# Sheet_1.net
KiCad netlist of a schematic drawn in Altium Designer
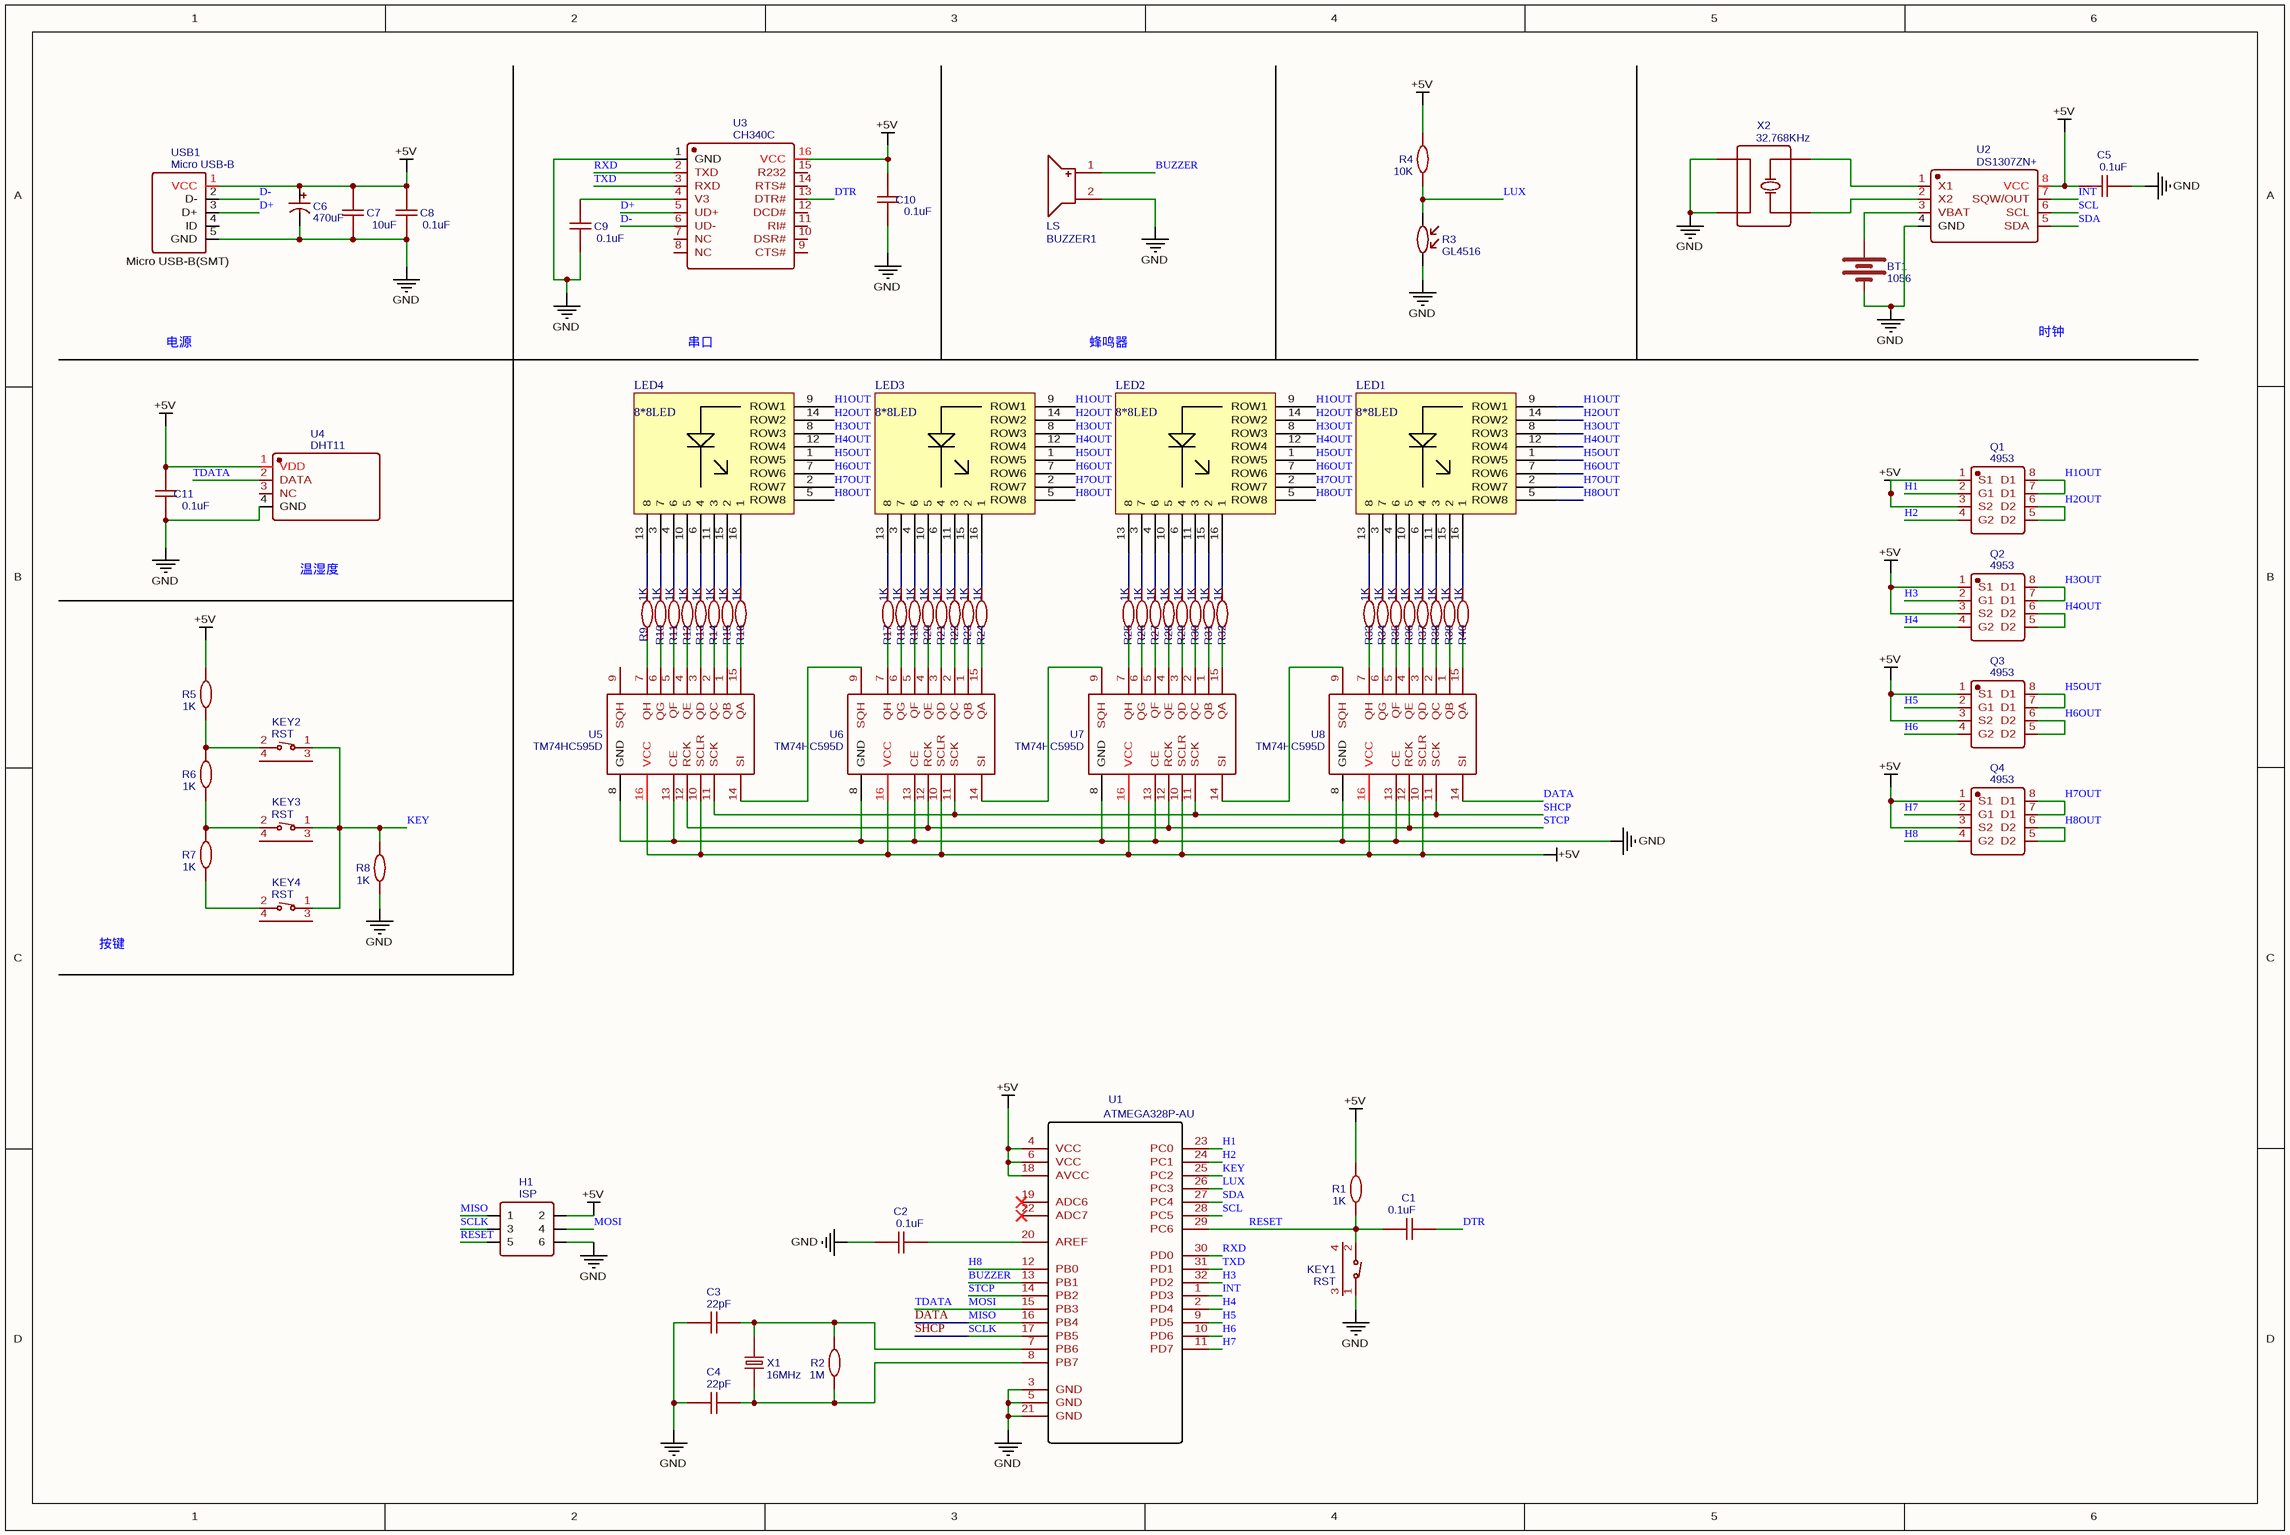
[diagram p0: Sheet_1.schdoc]

(export (version "E")
  (design (tool "Eeschema 10.0.6"))
  (components
    (comp (ref "BT1")
      (value "1056")
      (footprint "KEYSTONE_1056")
      (fields (field (name "BOM_SUPPLIER PART") "C238067"))
      (libsource (lib "altium-import") (part "root_3_1056_"))
    )
    (comp (ref "BUZZER1")
      (value "LS")
      (footprint "BUZZER-R6.0-2P-7.6MM")
      (fields
        (field (name "BOM_SUPPLIER PART") "C252943")
        (field (name "BOM_MANUFACTURER PART") "GMD12095YB-24V2400")
      )
      (libsource (lib "altium-import") (part "root_0_LS_"))
    )
    (comp (ref "C1")
      (value "0.1uF")
      (footprint "0603")
      (fields
        (field (name "BOM_SUPPLIER PART") "C138344")
        (field (name "BOM_MANUFACTURER PART") "CT41-0603-2F4-50V-0.1uF-M(N)")
      )
      (libsource (lib "altium-import") (part "root_1_0.1uF_"))
    )
    (comp (ref "C2")
      (value "0.1uF")
      (footprint "0603")
      (fields
        (field (name "BOM_SUPPLIER PART") "C138344")
        (field (name "BOM_MANUFACTURER PART") "CT41-0603-2F4-50V-0.1uF-M(N)")
      )
      (libsource (lib "altium-import") (part "root_1_0.1uF_"))
    )
    (comp (ref "C3")
      (value "22pF")
      (footprint "0603")
      (fields
        (field (name "BOM_MANUFACTURER PART") "0603CG220J500NT")
        (field (name "BOM_SUPPLIER PART") "C91701")
      )
      (libsource (lib "altium-import") (part "root_0_22pF_"))
    )
    (comp (ref "C4")
      (value "22pF")
      (footprint "0603")
      (fields
        (field (name "BOM_MANUFACTURER PART") "0603CG220J500NT")
        (field (name "BOM_SUPPLIER PART") "C91701")
      )
      (libsource (lib "altium-import") (part "root_0_22pF_"))
    )
    (comp (ref "C5")
      (value "0.1uF")
      (footprint "0603")
      (fields
        (field (name "BOM_SUPPLIER PART") "C138344")
        (field (name "BOM_MANUFACTURER PART") "CT41-0603-2F4-50V-0.1uF-M(N)")
      )
      (libsource (lib "altium-import") (part "root_3_0.1uF_"))
    )
    (comp (ref "C6")
      (value "470uF")
      (footprint "CASE-D_7343")
      (fields
        (field (name "BOM_MANUFACTURER PART") "T520D477M006ATE025")
        (field (name "BOM_SUPPLIER PART") "C156460")
      )
      (libsource (lib "altium-import") (part "root_3_470uF_"))
    )
    (comp (ref "C7")
      (value "10uF")
      (footprint "0603")
      (fields
        (field (name "BOM_SUPPLIER PART") "C138344")
        (field (name "BOM_MANUFACTURER PART") "CT41-0603-2F4-50V-0.1uF-M(N)")
      )
      (libsource (lib "altium-import") (part "root_2_10uF_"))
    )
    (comp (ref "C8")
      (value "0.1uF")
      (footprint "0603")
      (fields
        (field (name "BOM_SUPPLIER PART") "C138344")
        (field (name "BOM_MANUFACTURER PART") "CT41-0603-2F4-50V-0.1uF-M(N)")
      )
      (libsource (lib "altium-import") (part "root_2_0.1uF_"))
    )
    (comp (ref "C9")
      (value "0.1uF")
      (footprint "0603")
      (fields
        (field (name "BOM_SUPPLIER PART") "C138344")
        (field (name "BOM_MANUFACTURER PART") "CT41-0603-2F4-50V-0.1uF-M(N)")
      )
      (libsource (lib "altium-import") (part "root_2_0.1uF_"))
    )
    (comp (ref "C10")
      (value "0.1uF")
      (footprint "0603")
      (fields
        (field (name "BOM_SUPPLIER PART") "C138344")
        (field (name "BOM_MANUFACTURER PART") "CT41-0603-2F4-50V-0.1uF-M(N)")
      )
      (libsource (lib "altium-import") (part "root_2_0.1uF_"))
    )
    (comp (ref "C11")
      (value "0.1uF")
      (footprint "0603")
      (fields
        (field (name "BOM_SUPPLIER PART") "C138344")
        (field (name "BOM_MANUFACTURER PART") "CT41-0603-2F4-50V-0.1uF-M(N)")
      )
      (libsource (lib "altium-import") (part "root_2_0.1uF_"))
    )
    (comp (ref "H1")
      (value "ISP")
      (footprint "HDR-3X2/2.54")
      (fields
        (field (name "BOM_MANUFACTURER PART") "DS1023-2*3SF11")
        (field (name "BOM_SUPPLIER PART") "C92272")
      )
      (libsource (lib "altium-import") (part "root_0_ISP_"))
    )
    (comp (ref "KEY1")
      (value "RST")
      (footprint "SW-TH_BBJ6X6X5PH260G")
      (fields
        (field (name "BOM_SUPPLIER PART") "C71832")
        (field (name "BOM_MANUFACTURER PART") "Switch,6*6*5Plastic head,260G, 0.25mm,Side foot")
      )
      (libsource (lib "altium-import") (part "root_1_RST_"))
    )
    (comp (ref "KEY2")
      (value "RST")
      (footprint "SW-TH_BBJ6X6X5PH260G")
      (fields
        (field (name "BOM_SUPPLIER PART") "C71832")
        (field (name "BOM_MANUFACTURER PART") "Switch,6*6*5Plastic head,260G, 0.25mm,Side foot")
      )
      (libsource (lib "altium-import") (part "root_2_RST_"))
    )
    (comp (ref "KEY3")
      (value "RST")
      (footprint "SW-TH_BBJ6X6X5PH260G")
      (fields
        (field (name "BOM_SUPPLIER PART") "C71832")
        (field (name "BOM_MANUFACTURER PART") "Switch,6*6*5Plastic head,260G, 0.25mm,Side foot")
      )
      (libsource (lib "altium-import") (part "root_2_RST_"))
    )
    (comp (ref "KEY4")
      (value "RST")
      (footprint "SW-TH_BBJ6X6X5PH260G")
      (fields
        (field (name "BOM_SUPPLIER PART") "C71832")
        (field (name "BOM_MANUFACTURER PART") "Switch,6*6*5Plastic head,260G, 0.25mm,Side foot")
      )
      (libsource (lib "altium-import") (part "root_2_RST_"))
    )
    (comp (ref "LED1") (value "8*8LED") (footprint "8X8LED") (libsource (lib "Sheet_1") (part "8*8LED")))
    (comp (ref "LED2") (value "8*8LED") (footprint "8X8LED") (libsource (lib "Sheet_1") (part "8*8LED")))
    (comp (ref "LED3") (value "8*8LED") (footprint "8X8LED") (libsource (lib "Sheet_1") (part "8*8LED")))
    (comp (ref "LED4") (value "8*8LED") (footprint "8X8LED") (libsource (lib "Sheet_1") (part "8*8LED")))
    (comp (ref "Q1")
      (value "4953")
      (footprint "SOP-8")
      (fields (field (name "BOM_SUPPLIER PART") "C181099"))
      (libsource (lib "altium-import") (part "root_0_4953_"))
    )
    (comp (ref "Q2")
      (value "4953")
      (footprint "SOP-8")
      (fields (field (name "BOM_SUPPLIER PART") "C181099"))
      (libsource (lib "altium-import") (part "root_0_4953_"))
    )
    (comp (ref "Q3")
      (value "4953")
      (footprint "SOP-8")
      (fields (field (name "BOM_SUPPLIER PART") "C181099"))
      (libsource (lib "altium-import") (part "root_0_4953_"))
    )
    (comp (ref "Q4")
      (value "4953")
      (footprint "SOP-8")
      (fields (field (name "BOM_SUPPLIER PART") "C181099"))
      (libsource (lib "altium-import") (part "root_0_4953_"))
    )
    (comp (ref "R1")
      (value "1K")
      (footprint "0603")
      (fields
        (field (name "BOM_SUPPLIER PART") "C188364")
        (field (name "BOM_MANUFACTURER PART") "TR0603B1KP0525")
      )
      (libsource (lib "altium-import") (part "root_1_1K_"))
    )
    (comp (ref "R2")
      (value "1M")
      (footprint "0603")
      (fields
        (field (name "BOM_SUPPLIER PART") "C188364")
        (field (name "BOM_MANUFACTURER PART") "TR0603B1KP0525")
      )
      (libsource (lib "altium-import") (part "root_1_1M_"))
    )
    (comp (ref "R3")
      (value "GL4516")
      (footprint "RES-TH_L4.30-W3.60-L")
      (fields (field (name "BOM_SUPPLIER PART") "C125632"))
      (libsource (lib "altium-import") (part "root_3_GL4516_"))
    )
    (comp (ref "R4")
      (value "10K")
      (footprint "0603")
      (fields
        (field (name "BOM_SUPPLIER PART") "C188364")
        (field (name "BOM_MANUFACTURER PART") "TR0603B1KP0525")
      )
      (libsource (lib "altium-import") (part "root_1_10K_"))
    )
    (comp (ref "R5")
      (value "1K")
      (footprint "0603")
      (fields
        (field (name "BOM_SUPPLIER PART") "C188364")
        (field (name "BOM_MANUFACTURER PART") "TR0603B1KP0525")
      )
      (libsource (lib "altium-import") (part "root_1_1K_"))
    )
    (comp (ref "R6")
      (value "1K")
      (footprint "0603")
      (fields
        (field (name "BOM_SUPPLIER PART") "C188364")
        (field (name "BOM_MANUFACTURER PART") "TR0603B1KP0525")
      )
      (libsource (lib "altium-import") (part "root_1_1K_"))
    )
    (comp (ref "R7")
      (value "1K")
      (footprint "0603")
      (fields
        (field (name "BOM_SUPPLIER PART") "C188364")
        (field (name "BOM_MANUFACTURER PART") "TR0603B1KP0525")
      )
      (libsource (lib "altium-import") (part "root_1_1K_"))
    )
    (comp (ref "R8")
      (value "1K")
      (footprint "0603")
      (fields
        (field (name "BOM_SUPPLIER PART") "C188364")
        (field (name "BOM_MANUFACTURER PART") "TR0603B1KP0525")
      )
      (libsource (lib "altium-import") (part "root_1_1K_"))
    )
    (comp (ref "R9")
      (value "1K")
      (footprint "0603")
      (fields
        (field (name "BOM_SUPPLIER PART") "C188364")
        (field (name "BOM_MANUFACTURER PART") "TR0603B1KP0525")
      )
      (libsource (lib "altium-import") (part "root_1_1K_"))
    )
    (comp (ref "R10")
      (value "1K")
      (footprint "0603")
      (fields
        (field (name "BOM_SUPPLIER PART") "C188364")
        (field (name "BOM_MANUFACTURER PART") "TR0603B1KP0525")
      )
      (libsource (lib "altium-import") (part "root_1_1K_"))
    )
    (comp (ref "R11")
      (value "1K")
      (footprint "0603")
      (fields
        (field (name "BOM_SUPPLIER PART") "C188364")
        (field (name "BOM_MANUFACTURER PART") "TR0603B1KP0525")
      )
      (libsource (lib "altium-import") (part "root_1_1K_"))
    )
    (comp (ref "R12")
      (value "1K")
      (footprint "0603")
      (fields
        (field (name "BOM_SUPPLIER PART") "C188364")
        (field (name "BOM_MANUFACTURER PART") "TR0603B1KP0525")
      )
      (libsource (lib "altium-import") (part "root_1_1K_"))
    )
    (comp (ref "R13")
      (value "1K")
      (footprint "0603")
      (fields
        (field (name "BOM_SUPPLIER PART") "C188364")
        (field (name "BOM_MANUFACTURER PART") "TR0603B1KP0525")
      )
      (libsource (lib "altium-import") (part "root_1_1K_"))
    )
    (comp (ref "R14")
      (value "1K")
      (footprint "0603")
      (fields
        (field (name "BOM_SUPPLIER PART") "C188364")
        (field (name "BOM_MANUFACTURER PART") "TR0603B1KP0525")
      )
      (libsource (lib "altium-import") (part "root_1_1K_"))
    )
    (comp (ref "R15")
      (value "1K")
      (footprint "0603")
      (fields
        (field (name "BOM_SUPPLIER PART") "C188364")
        (field (name "BOM_MANUFACTURER PART") "TR0603B1KP0525")
      )
      (libsource (lib "altium-import") (part "root_1_1K_"))
    )
    (comp (ref "R16")
      (value "1K")
      (footprint "0603")
      (fields
        (field (name "BOM_SUPPLIER PART") "C188364")
        (field (name "BOM_MANUFACTURER PART") "TR0603B1KP0525")
      )
      (libsource (lib "altium-import") (part "root_1_1K_"))
    )
    (comp (ref "R17")
      (value "1K")
      (footprint "0603")
      (fields
        (field (name "BOM_SUPPLIER PART") "C188364")
        (field (name "BOM_MANUFACTURER PART") "TR0603B1KP0525")
      )
      (libsource (lib "altium-import") (part "root_1_1K_"))
    )
    (comp (ref "R18")
      (value "1K")
      (footprint "0603")
      (fields
        (field (name "BOM_SUPPLIER PART") "C188364")
        (field (name "BOM_MANUFACTURER PART") "TR0603B1KP0525")
      )
      (libsource (lib "altium-import") (part "root_1_1K_"))
    )
    (comp (ref "R19")
      (value "1K")
      (footprint "0603")
      (fields
        (field (name "BOM_SUPPLIER PART") "C188364")
        (field (name "BOM_MANUFACTURER PART") "TR0603B1KP0525")
      )
      (libsource (lib "altium-import") (part "root_1_1K_"))
    )
    (comp (ref "R20")
      (value "1K")
      (footprint "0603")
      (fields
        (field (name "BOM_SUPPLIER PART") "C188364")
        (field (name "BOM_MANUFACTURER PART") "TR0603B1KP0525")
      )
      (libsource (lib "altium-import") (part "root_1_1K_"))
    )
    (comp (ref "R21")
      (value "1K")
      (footprint "0603")
      (fields
        (field (name "BOM_SUPPLIER PART") "C188364")
        (field (name "BOM_MANUFACTURER PART") "TR0603B1KP0525")
      )
      (libsource (lib "altium-import") (part "root_1_1K_"))
    )
    (comp (ref "R22")
      (value "1K")
      (footprint "0603")
      (fields
        (field (name "BOM_SUPPLIER PART") "C188364")
        (field (name "BOM_MANUFACTURER PART") "TR0603B1KP0525")
      )
      (libsource (lib "altium-import") (part "root_1_1K_"))
    )
    (comp (ref "R23")
      (value "1K")
      (footprint "0603")
      (fields
        (field (name "BOM_SUPPLIER PART") "C188364")
        (field (name "BOM_MANUFACTURER PART") "TR0603B1KP0525")
      )
      (libsource (lib "altium-import") (part "root_1_1K_"))
    )
    (comp (ref "R24")
      (value "1K")
      (footprint "0603")
      (fields
        (field (name "BOM_SUPPLIER PART") "C188364")
        (field (name "BOM_MANUFACTURER PART") "TR0603B1KP0525")
      )
      (libsource (lib "altium-import") (part "root_1_1K_"))
    )
    (comp (ref "R25")
      (value "1K")
      (footprint "0603")
      (fields
        (field (name "BOM_SUPPLIER PART") "C188364")
        (field (name "BOM_MANUFACTURER PART") "TR0603B1KP0525")
      )
      (libsource (lib "altium-import") (part "root_1_1K_"))
    )
    (comp (ref "R26")
      (value "1K")
      (footprint "0603")
      (fields
        (field (name "BOM_SUPPLIER PART") "C188364")
        (field (name "BOM_MANUFACTURER PART") "TR0603B1KP0525")
      )
      (libsource (lib "altium-import") (part "root_1_1K_"))
    )
    (comp (ref "R27")
      (value "1K")
      (footprint "0603")
      (fields
        (field (name "BOM_SUPPLIER PART") "C188364")
        (field (name "BOM_MANUFACTURER PART") "TR0603B1KP0525")
      )
      (libsource (lib "altium-import") (part "root_1_1K_"))
    )
    (comp (ref "R28")
      (value "1K")
      (footprint "0603")
      (fields
        (field (name "BOM_SUPPLIER PART") "C188364")
        (field (name "BOM_MANUFACTURER PART") "TR0603B1KP0525")
      )
      (libsource (lib "altium-import") (part "root_1_1K_"))
    )
    (comp (ref "R29")
      (value "1K")
      (footprint "0603")
      (fields
        (field (name "BOM_SUPPLIER PART") "C188364")
        (field (name "BOM_MANUFACTURER PART") "TR0603B1KP0525")
      )
      (libsource (lib "altium-import") (part "root_1_1K_"))
    )
    (comp (ref "R30")
      (value "1K")
      (footprint "0603")
      (fields
        (field (name "BOM_SUPPLIER PART") "C188364")
        (field (name "BOM_MANUFACTURER PART") "TR0603B1KP0525")
      )
      (libsource (lib "altium-import") (part "root_1_1K_"))
    )
    (comp (ref "R31")
      (value "1K")
      (footprint "0603")
      (fields
        (field (name "BOM_SUPPLIER PART") "C188364")
        (field (name "BOM_MANUFACTURER PART") "TR0603B1KP0525")
      )
      (libsource (lib "altium-import") (part "root_1_1K_"))
    )
    (comp (ref "R32")
      (value "1K")
      (footprint "0603")
      (fields
        (field (name "BOM_SUPPLIER PART") "C188364")
        (field (name "BOM_MANUFACTURER PART") "TR0603B1KP0525")
      )
      (libsource (lib "altium-import") (part "root_1_1K_"))
    )
    (comp (ref "R33")
      (value "1K")
      (footprint "0603")
      (fields
        (field (name "BOM_SUPPLIER PART") "C188364")
        (field (name "BOM_MANUFACTURER PART") "TR0603B1KP0525")
      )
      (libsource (lib "altium-import") (part "root_1_1K_"))
    )
    (comp (ref "R34")
      (value "1K")
      (footprint "0603")
      (fields
        (field (name "BOM_SUPPLIER PART") "C188364")
        (field (name "BOM_MANUFACTURER PART") "TR0603B1KP0525")
      )
      (libsource (lib "altium-import") (part "root_1_1K_"))
    )
    (comp (ref "R35")
      (value "1K")
      (footprint "0603")
      (fields
        (field (name "BOM_SUPPLIER PART") "C188364")
        (field (name "BOM_MANUFACTURER PART") "TR0603B1KP0525")
      )
      (libsource (lib "altium-import") (part "root_1_1K_"))
    )
    (comp (ref "R36")
      (value "1K")
      (footprint "0603")
      (fields
        (field (name "BOM_SUPPLIER PART") "C188364")
        (field (name "BOM_MANUFACTURER PART") "TR0603B1KP0525")
      )
      (libsource (lib "altium-import") (part "root_1_1K_"))
    )
    (comp (ref "R37")
      (value "1K")
      (footprint "0603")
      (fields
        (field (name "BOM_SUPPLIER PART") "C188364")
        (field (name "BOM_MANUFACTURER PART") "TR0603B1KP0525")
      )
      (libsource (lib "altium-import") (part "root_1_1K_"))
    )
    (comp (ref "R38")
      (value "1K")
      (footprint "0603")
      (fields
        (field (name "BOM_SUPPLIER PART") "C188364")
        (field (name "BOM_MANUFACTURER PART") "TR0603B1KP0525")
      )
      (libsource (lib "altium-import") (part "root_1_1K_"))
    )
    (comp (ref "R39")
      (value "1K")
      (footprint "0603")
      (fields
        (field (name "BOM_SUPPLIER PART") "C188364")
        (field (name "BOM_MANUFACTURER PART") "TR0603B1KP0525")
      )
      (libsource (lib "altium-import") (part "root_1_1K_"))
    )
    (comp (ref "R40")
      (value "1K")
      (footprint "0603")
      (fields
        (field (name "BOM_SUPPLIER PART") "C188364")
        (field (name "BOM_MANUFACTURER PART") "TR0603B1KP0525")
      )
      (libsource (lib "altium-import") (part "root_1_1K_"))
    )
    (comp (ref "U1")
      (value "ATMEGA328P-AU")
      (footprint "TQFP-32_7X7X08P")
      (fields (field (name "BOM_SUPPLIER PART") "C14877"))
      (libsource (lib "altium-import") (part "root_0_ATMEGA328P-AU_"))
    )
    (comp (ref "U2")
      (value "DS1307ZN+")
      (footprint "SOP-8_150MIL")
      (fields (field (name "BOM_SUPPLIER PART") "C26858"))
      (libsource (lib "altium-import") (part "root_0_DS1307ZN+_"))
    )
    (comp (ref "U3")
      (value "CH340C")
      (footprint "SOP-16_150MIL")
      (fields (field (name "BOM_SUPPLIER PART") "C84681"))
      (libsource (lib "altium-import") (part "root_0_CH340C_"))
    )
    (comp (ref "U4")
      (value "DHT11")
      (footprint "DHT11")
      (fields (field (name "BOM_SUPPLIER PART") "C117051"))
      (libsource (lib "altium-import") (part "root_0_DHT11_"))
    )
    (comp (ref "U5")
      (value "TM74HC595D")
      (footprint "SOP-16_150MIL")
      (fields (field (name "BOM_SUPPLIER PART") "C79097"))
      (libsource (lib "altium-import") (part "root_1_TM74HC595D_"))
    )
    (comp (ref "U6")
      (value "TM74HC595D")
      (footprint "SOP-16_150MIL")
      (fields (field (name "BOM_SUPPLIER PART") "C79097"))
      (libsource (lib "altium-import") (part "root_1_TM74HC595D_"))
    )
    (comp (ref "U7")
      (value "TM74HC595D")
      (footprint "SOP-16_150MIL")
      (fields (field (name "BOM_SUPPLIER PART") "C79097"))
      (libsource (lib "altium-import") (part "root_1_TM74HC595D_"))
    )
    (comp (ref "U8")
      (value "TM74HC595D")
      (footprint "SOP-16_150MIL")
      (fields (field (name "BOM_SUPPLIER PART") "C79097"))
      (libsource (lib "altium-import") (part "root_1_TM74HC595D_"))
    )
    (comp (ref "USB1")
      (value "Micro USB-B")
      (footprint "MICRO-USB-12")
      (fields
        (field (name "BOM_MANUFACTURER PART") "Micro USB-B 5P_C40942")
        (field (name "BOM_SUPPLIER PART") "C40942")
      )
      (libsource (lib "altium-import") (part "root_0_Micro USB-B_"))
    )
    (comp (ref "X1")
      (value "16MHz")
      (footprint "49S-CRYSTAL")
      (fields
        (field (name "BOM_SUPPLIER PART") "C295075")
        (field (name "BOM_MANUFACTURER PART") "XIHCELNANF-16MHZ")
      )
      (libsource (lib "altium-import") (part "root_3_16MHz_"))
    )
    (comp (ref "X2")
      (value "32.768KHz")
      (footprint "MC-146")
      (fields
        (field (name "BOM_MANUFACTURER PART") "MC-14632.768kHz7.0pF20PPM")
        (field (name "BOM_SUPPLIER PART") "C94977")
      )
      (libsource (lib "altium-import") (part "root_2_32.768KHz_"))
    )
  )
  (nets
    (net (code "1") (name "+5V") (class "Default")
      (node (ref "C10") (pin "2") (pinfunction "2_2") (pintype "passive"))
      (node (ref "C11") (pin "2") (pinfunction "2_2") (pintype "passive"))
      (node (ref "C5") (pin "2") (pinfunction "2_2") (pintype "passive"))
      (node (ref "C6") (pin "1") (pinfunction "1_1") (pintype "passive"))
      (node (ref "C7") (pin "2") (pinfunction "2_2") (pintype "passive"))
      (node (ref "C8") (pin "2") (pinfunction "2_2") (pintype "passive"))
      (node (ref "H1") (pin "2") (pinfunction "2_2") (pintype "passive"))
      (node (ref "Q1") (pin "1") (pinfunction "S1_1") (pintype "passive"))
      (node (ref "Q1") (pin "3") (pinfunction "S2_3") (pintype "passive"))
      (node (ref "Q2") (pin "1") (pinfunction "S1_1") (pintype "passive"))
      (node (ref "Q2") (pin "3") (pinfunction "S2_3") (pintype "passive"))
      (node (ref "Q3") (pin "1") (pinfunction "S1_1") (pintype "passive"))
      (node (ref "Q3") (pin "3") (pinfunction "S2_3") (pintype "passive"))
      (node (ref "Q4") (pin "1") (pinfunction "S1_1") (pintype "passive"))
      (node (ref "Q4") (pin "3") (pinfunction "S2_3") (pintype "passive"))
      (node (ref "R1") (pin "2") (pinfunction "2_2") (pintype "passive"))
      (node (ref "R4") (pin "2") (pinfunction "2_2") (pintype "passive"))
      (node (ref "R5") (pin "2") (pinfunction "2_2") (pintype "passive"))
      (node (ref "U1") (pin "18") (pinfunction "AVCC_18") (pintype "passive"))
      (node (ref "U1") (pin "4") (pinfunction "VCC_4") (pintype "passive"))
      (node (ref "U1") (pin "6") (pinfunction "VCC_6") (pintype "passive"))
      (node (ref "U2") (pin "8") (pinfunction "VCC_8") (pintype "passive"))
      (node (ref "U3") (pin "16") (pinfunction "VCC_16") (pintype "passive"))
      (node (ref "U4") (pin "1") (pinfunction "VDD_1") (pintype "passive"))
      (node (ref "U5") (pin "10") (pinfunction "SCLR_10") (pintype "passive"))
      (node (ref "U5") (pin "16") (pinfunction "VCC_16") (pintype "passive"))
      (node (ref "U6") (pin "10") (pinfunction "SCLR_10") (pintype "passive"))
      (node (ref "U6") (pin "16") (pinfunction "VCC_16") (pintype "passive"))
      (node (ref "U7") (pin "10") (pinfunction "SCLR_10") (pintype "passive"))
      (node (ref "U7") (pin "16") (pinfunction "VCC_16") (pintype "passive"))
      (node (ref "U8") (pin "10") (pinfunction "SCLR_10") (pintype "passive"))
      (node (ref "U8") (pin "16") (pinfunction "VCC_16") (pintype "passive"))
      (node (ref "USB1") (pin "1") (pinfunction "VCC_1") (pintype "passive"))
    )
    (net (code "2") (name "/BUZZER") (class "Default")
      (node (ref "BUZZER1") (pin "1") (pinfunction "1_1") (pintype "passive"))
      (node (ref "U1") (pin "13") (pinfunction "PB1_13") (pintype "passive"))
    )
    (net (code "3") (name "/D+") (class "Default")
      (node (ref "U3") (pin "5") (pinfunction "UD+_5") (pintype "passive"))
      (node (ref "USB1") (pin "3") (pinfunction "D+_3") (pintype "passive"))
    )
    (net (code "4") (name "/D-") (class "Default")
      (node (ref "U3") (pin "6") (pinfunction "UD-_6") (pintype "passive"))
      (node (ref "USB1") (pin "2") (pinfunction "D-_2") (pintype "passive"))
    )
    (net (code "5") (name "/DATA") (class "Default")
      (node (ref "H1") (pin "1") (pinfunction "1_1") (pintype "passive"))
      (node (ref "U1") (pin "16") (pinfunction "PB4_16") (pintype "passive"))
      (node (ref "U8") (pin "14") (pinfunction "SI_14") (pintype "passive"))
    )
    (net (code "6") (name "/DTR") (class "Default")
      (node (ref "C1") (pin "2") (pinfunction "2_2") (pintype "passive"))
      (node (ref "U3") (pin "13") (pinfunction "DTR#_13") (pintype "passive"))
    )
    (net (code "7") (name "/H1") (class "Default")
      (node (ref "Q1") (pin "2") (pinfunction "G1_2") (pintype "passive"))
      (node (ref "U1") (pin "23") (pinfunction "PC0_23") (pintype "passive"))
    )
    (net (code "8") (name "/H1OUT") (class "Default")
      (node (ref "LED1") (pin "9") (pinfunction "ROW1_9") (pintype "passive"))
      (node (ref "LED2") (pin "9") (pinfunction "ROW1_9") (pintype "passive"))
      (node (ref "LED3") (pin "9") (pinfunction "ROW1_9") (pintype "passive"))
      (node (ref "LED4") (pin "9") (pinfunction "ROW1_9") (pintype "passive"))
      (node (ref "Q1") (pin "7") (pinfunction "D1_7") (pintype "passive"))
      (node (ref "Q1") (pin "8") (pinfunction "D1_8") (pintype "passive"))
    )
    (net (code "9") (name "/H2") (class "Default")
      (node (ref "Q1") (pin "4") (pinfunction "G2_4") (pintype "passive"))
      (node (ref "U1") (pin "24") (pinfunction "PC1_24") (pintype "passive"))
    )
    (net (code "10") (name "/H2OUT") (class "Default")
      (node (ref "LED1") (pin "14") (pinfunction "ROW2_14") (pintype "passive"))
      (node (ref "LED2") (pin "14") (pinfunction "ROW2_14") (pintype "passive"))
      (node (ref "LED3") (pin "14") (pinfunction "ROW2_14") (pintype "passive"))
      (node (ref "LED4") (pin "14") (pinfunction "ROW2_14") (pintype "passive"))
      (node (ref "Q1") (pin "5") (pinfunction "D2_5") (pintype "passive"))
      (node (ref "Q1") (pin "6") (pinfunction "D2_6") (pintype "passive"))
    )
    (net (code "11") (name "/H3") (class "Default")
      (node (ref "Q2") (pin "2") (pinfunction "G1_2") (pintype "passive"))
      (node (ref "U1") (pin "32") (pinfunction "PD2_32") (pintype "passive"))
    )
    (net (code "12") (name "/H3OUT") (class "Default")
      (node (ref "LED1") (pin "8") (pinfunction "ROW3_8") (pintype "passive"))
      (node (ref "LED2") (pin "8") (pinfunction "ROW3_8") (pintype "passive"))
      (node (ref "LED3") (pin "8") (pinfunction "ROW3_8") (pintype "passive"))
      (node (ref "LED4") (pin "8") (pinfunction "ROW3_8") (pintype "passive"))
      (node (ref "Q2") (pin "7") (pinfunction "D1_7") (pintype "passive"))
      (node (ref "Q2") (pin "8") (pinfunction "D1_8") (pintype "passive"))
    )
    (net (code "13") (name "/H4") (class "Default")
      (node (ref "Q2") (pin "4") (pinfunction "G2_4") (pintype "passive"))
      (node (ref "U1") (pin "2") (pinfunction "PD4_2") (pintype "passive"))
    )
    (net (code "14") (name "/H4OUT") (class "Default")
      (node (ref "LED1") (pin "12") (pinfunction "ROW4_12") (pintype "passive"))
      (node (ref "LED2") (pin "12") (pinfunction "ROW4_12") (pintype "passive"))
      (node (ref "LED3") (pin "12") (pinfunction "ROW4_12") (pintype "passive"))
      (node (ref "LED4") (pin "12") (pinfunction "ROW4_12") (pintype "passive"))
      (node (ref "Q2") (pin "5") (pinfunction "D2_5") (pintype "passive"))
      (node (ref "Q2") (pin "6") (pinfunction "D2_6") (pintype "passive"))
    )
    (net (code "15") (name "/H5") (class "Default")
      (node (ref "Q3") (pin "2") (pinfunction "G1_2") (pintype "passive"))
      (node (ref "U1") (pin "9") (pinfunction "PD5_9") (pintype "passive"))
    )
    (net (code "16") (name "/H5OUT") (class "Default")
      (node (ref "LED1") (pin "1") (pinfunction "ROW5_1") (pintype "passive"))
      (node (ref "LED2") (pin "1") (pinfunction "ROW5_1") (pintype "passive"))
      (node (ref "LED3") (pin "1") (pinfunction "ROW5_1") (pintype "passive"))
      (node (ref "LED4") (pin "1") (pinfunction "ROW5_1") (pintype "passive"))
      (node (ref "Q3") (pin "7") (pinfunction "D1_7") (pintype "passive"))
      (node (ref "Q3") (pin "8") (pinfunction "D1_8") (pintype "passive"))
    )
    (net (code "17") (name "/H6") (class "Default")
      (node (ref "Q3") (pin "4") (pinfunction "G2_4") (pintype "passive"))
      (node (ref "U1") (pin "10") (pinfunction "PD6_10") (pintype "passive"))
    )
    (net (code "18") (name "/H6OUT") (class "Default")
      (node (ref "LED1") (pin "7") (pinfunction "ROW6_7") (pintype "passive"))
      (node (ref "LED2") (pin "7") (pinfunction "ROW6_7") (pintype "passive"))
      (node (ref "LED3") (pin "7") (pinfunction "ROW6_7") (pintype "passive"))
      (node (ref "LED4") (pin "7") (pinfunction "ROW6_7") (pintype "passive"))
      (node (ref "Q3") (pin "5") (pinfunction "D2_5") (pintype "passive"))
      (node (ref "Q3") (pin "6") (pinfunction "D2_6") (pintype "passive"))
    )
    (net (code "19") (name "/H7") (class "Default")
      (node (ref "Q4") (pin "2") (pinfunction "G1_2") (pintype "passive"))
      (node (ref "U1") (pin "11") (pinfunction "PD7_11") (pintype "passive"))
    )
    (net (code "20") (name "/H7OUT") (class "Default")
      (node (ref "LED1") (pin "2") (pinfunction "ROW7_2") (pintype "passive"))
      (node (ref "LED2") (pin "2") (pinfunction "ROW7_2") (pintype "passive"))
      (node (ref "LED3") (pin "2") (pinfunction "ROW7_2") (pintype "passive"))
      (node (ref "LED4") (pin "2") (pinfunction "ROW7_2") (pintype "passive"))
      (node (ref "Q4") (pin "7") (pinfunction "D1_7") (pintype "passive"))
      (node (ref "Q4") (pin "8") (pinfunction "D1_8") (pintype "passive"))
    )
    (net (code "21") (name "/H8") (class "Default")
      (node (ref "Q4") (pin "4") (pinfunction "G2_4") (pintype "passive"))
      (node (ref "U1") (pin "12") (pinfunction "PB0_12") (pintype "passive"))
    )
    (net (code "22") (name "/H8OUT") (class "Default")
      (node (ref "LED1") (pin "5") (pinfunction "ROW8_5") (pintype "passive"))
      (node (ref "LED2") (pin "5") (pinfunction "ROW8_5") (pintype "passive"))
      (node (ref "LED3") (pin "5") (pinfunction "ROW8_5") (pintype "passive"))
      (node (ref "LED4") (pin "5") (pinfunction "ROW8_5") (pintype "passive"))
      (node (ref "Q4") (pin "5") (pinfunction "D2_5") (pintype "passive"))
      (node (ref "Q4") (pin "6") (pinfunction "D2_6") (pintype "passive"))
    )
    (net (code "23") (name "/INT") (class "Default")
      (node (ref "U1") (pin "1") (pinfunction "PD3_1") (pintype "passive"))
      (node (ref "U2") (pin "7") (pinfunction "SQW/OUT_7") (pintype "passive"))
    )
    (net (code "24") (name "/KEY") (class "Default")
      (node (ref "KEY2") (pin "1") (pinfunction "1_1") (pintype "passive"))
      (node (ref "KEY3") (pin "1") (pinfunction "1_1") (pintype "passive"))
      (node (ref "KEY4") (pin "1") (pinfunction "1_1") (pintype "passive"))
      (node (ref "R8") (pin "2") (pinfunction "2_2") (pintype "passive"))
      (node (ref "U1") (pin "25") (pinfunction "PC2_25") (pintype "passive"))
    )
    (net (code "25") (name "/LUX") (class "Default")
      (node (ref "R3") (pin "1") (pinfunction "1_1") (pintype "passive"))
      (node (ref "R4") (pin "1") (pinfunction "1_1") (pintype "passive"))
      (node (ref "U1") (pin "26") (pinfunction "PC3_26") (pintype "passive"))
    )
    (net (code "26") (name "/MOSI") (class "Default")
      (node (ref "H1") (pin "4") (pinfunction "4_4") (pintype "passive"))
      (node (ref "U1") (pin "15") (pinfunction "PB3_15") (pintype "passive"))
      (node (ref "U4") (pin "2") (pinfunction "DATA_2") (pintype "passive"))
    )
    (net (code "27") (name "/RESET") (class "Default")
      (node (ref "C1") (pin "1") (pinfunction "1_1") (pintype "passive"))
      (node (ref "H1") (pin "5") (pinfunction "5_5") (pintype "passive"))
      (node (ref "KEY1") (pin "2") (pinfunction "2_2") (pintype "passive"))
      (node (ref "R1") (pin "1") (pinfunction "1_1") (pintype "passive"))
      (node (ref "U1") (pin "29") (pinfunction "PC6_29") (pintype "passive"))
    )
    (net (code "28") (name "/RXD") (class "Default")
      (node (ref "U1") (pin "30") (pinfunction "PD0_30") (pintype "passive"))
      (node (ref "U3") (pin "2") (pinfunction "TXD_2") (pintype "passive"))
    )
    (net (code "29") (name "/SCL") (class "Default")
      (node (ref "U1") (pin "28") (pinfunction "PC5_28") (pintype "passive"))
      (node (ref "U2") (pin "6") (pinfunction "SCL_6") (pintype "passive"))
    )
    (net (code "30") (name "/SCLK") (class "Default")
      (node (ref "H1") (pin "3") (pinfunction "3_3") (pintype "passive"))
      (node (ref "U1") (pin "17") (pinfunction "PB5_17") (pintype "passive"))
      (node (ref "U5") (pin "11") (pinfunction "SCK_11") (pintype "passive"))
      (node (ref "U6") (pin "11") (pinfunction "SCK_11") (pintype "passive"))
      (node (ref "U7") (pin "11") (pinfunction "SCK_11") (pintype "passive"))
      (node (ref "U8") (pin "11") (pinfunction "SCK_11") (pintype "passive"))
    )
    (net (code "31") (name "/SDA") (class "Default")
      (node (ref "U1") (pin "27") (pinfunction "PC4_27") (pintype "passive"))
      (node (ref "U2") (pin "5") (pinfunction "SDA_5") (pintype "passive"))
    )
    (net (code "32") (name "/STCP") (class "Default")
      (node (ref "U1") (pin "14") (pinfunction "PB2_14") (pintype "passive"))
      (node (ref "U5") (pin "12") (pinfunction "RCK_12") (pintype "passive"))
      (node (ref "U6") (pin "12") (pinfunction "RCK_12") (pintype "passive"))
      (node (ref "U7") (pin "12") (pinfunction "RCK_12") (pintype "passive"))
      (node (ref "U8") (pin "12") (pinfunction "RCK_12") (pintype "passive"))
    )
    (net (code "33") (name "/TXD") (class "Default")
      (node (ref "U1") (pin "31") (pinfunction "PD1_31") (pintype "passive"))
      (node (ref "U3") (pin "3") (pinfunction "RXD_3") (pintype "passive"))
    )
    (net (code "34") (name "GND") (class "Default")
      (node (ref "BT1") (pin "2") (pinfunction "-_2") (pintype "passive"))
      (node (ref "BUZZER1") (pin "2") (pinfunction "2_2") (pintype "passive"))
      (node (ref "C10") (pin "1") (pinfunction "1_1") (pintype "passive"))
      (node (ref "C11") (pin "1") (pinfunction "1_1") (pintype "passive"))
      (node (ref "C2") (pin "1") (pinfunction "1_1") (pintype "passive"))
      (node (ref "C3") (pin "1") (pinfunction "1_1") (pintype "passive"))
      (node (ref "C4") (pin "1") (pinfunction "1_1") (pintype "passive"))
      (node (ref "C5") (pin "1") (pinfunction "1_1") (pintype "passive"))
      (node (ref "C6") (pin "2") (pinfunction "2_2") (pintype "passive"))
      (node (ref "C7") (pin "1") (pinfunction "1_1") (pintype "passive"))
      (node (ref "C8") (pin "1") (pinfunction "1_1") (pintype "passive"))
      (node (ref "C9") (pin "1") (pinfunction "1_1") (pintype "passive"))
      (node (ref "H1") (pin "6") (pinfunction "6_6") (pintype "passive"))
      (node (ref "KEY1") (pin "1") (pinfunction "1_1") (pintype "passive"))
      (node (ref "R3") (pin "2") (pinfunction "2_2") (pintype "passive"))
      (node (ref "R8") (pin "1") (pinfunction "1_1") (pintype "passive"))
      (node (ref "U1") (pin "21") (pinfunction "GND_21") (pintype "passive"))
      (node (ref "U1") (pin "3") (pinfunction "GND_3") (pintype "passive"))
      (node (ref "U1") (pin "5") (pinfunction "GND_5") (pintype "passive"))
      (node (ref "U2") (pin "4") (pinfunction "GND_4") (pintype "passive"))
      (node (ref "U3") (pin "1") (pinfunction "GND_1") (pintype "passive"))
      (node (ref "U4") (pin "4") (pinfunction "GND_4") (pintype "passive"))
      (node (ref "U5") (pin "13") (pinfunction "CE_13") (pintype "passive"))
      (node (ref "U5") (pin "8") (pinfunction "GND_8") (pintype "passive"))
      (node (ref "U6") (pin "13") (pinfunction "CE_13") (pintype "passive"))
      (node (ref "U6") (pin "8") (pinfunction "GND_8") (pintype "passive"))
      (node (ref "U7") (pin "13") (pinfunction "CE_13") (pintype "passive"))
      (node (ref "U7") (pin "8") (pinfunction "GND_8") (pintype "passive"))
      (node (ref "U8") (pin "13") (pinfunction "CE_13") (pintype "passive"))
      (node (ref "U8") (pin "8") (pinfunction "GND_8") (pintype "passive"))
      (node (ref "USB1") (pin "5") (pinfunction "GND_5") (pintype "passive"))
      (node (ref "X2") (pin "2") (pinfunction "GND_2") (pintype "passive"))
      (node (ref "X2") (pin "3") (pinfunction "GND_3") (pintype "passive"))
    )
    (net (code "35") (name "Net-(BT1-+)") (class "Default")
      (node (ref "BT1") (pin "1") (pinfunction "+_1") (pintype "passive"))
      (node (ref "U2") (pin "3") (pinfunction "VBAT_3") (pintype "passive"))
    )
    (net (code "36") (name "Net-(KEY2-Pad2)") (class "Default")
      (node (ref "KEY2") (pin "2") (pinfunction "2_2") (pintype "passive"))
      (node (ref "R5") (pin "1") (pinfunction "1_1") (pintype "passive"))
      (node (ref "R6") (pin "2") (pinfunction "2_2") (pintype "passive"))
    )
    (net (code "37") (name "Net-(KEY3-Pad2)") (class "Default")
      (node (ref "KEY3") (pin "2") (pinfunction "2_2") (pintype "passive"))
      (node (ref "R6") (pin "1") (pinfunction "1_1") (pintype "passive"))
      (node (ref "R7") (pin "2") (pinfunction "2_2") (pintype "passive"))
    )
    (net (code "38") (name "Net-(KEY4-Pad2)") (class "Default")
      (node (ref "KEY4") (pin "2") (pinfunction "2_2") (pintype "passive"))
      (node (ref "R7") (pin "1") (pinfunction "1_1") (pintype "passive"))
    )
    (net (code "39") (name "Net-(LED1-1)") (class "Default")
      (node (ref "LED1") (pin "16") (pinfunction "1_16") (pintype "passive"))
      (node (ref "R40") (pin "2") (pinfunction "2_2") (pintype "passive"))
    )
    (net (code "40") (name "Net-(LED1-2)") (class "Default")
      (node (ref "LED1") (pin "15") (pinfunction "2_15") (pintype "passive"))
      (node (ref "R39") (pin "2") (pinfunction "2_2") (pintype "passive"))
    )
    (net (code "41") (name "Net-(LED1-3)") (class "Default")
      (node (ref "LED1") (pin "11") (pinfunction "3_11") (pintype "passive"))
      (node (ref "R38") (pin "2") (pinfunction "2_2") (pintype "passive"))
    )
    (net (code "42") (name "Net-(LED1-4)") (class "Default")
      (node (ref "LED1") (pin "6") (pinfunction "4_6") (pintype "passive"))
      (node (ref "R37") (pin "2") (pinfunction "2_2") (pintype "passive"))
    )
    (net (code "43") (name "Net-(LED1-5)") (class "Default")
      (node (ref "LED1") (pin "10") (pinfunction "5_10") (pintype "passive"))
      (node (ref "R36") (pin "2") (pinfunction "2_2") (pintype "passive"))
    )
    (net (code "44") (name "Net-(LED1-6)") (class "Default")
      (node (ref "LED1") (pin "4") (pinfunction "6_4") (pintype "passive"))
      (node (ref "R35") (pin "2") (pinfunction "2_2") (pintype "passive"))
    )
    (net (code "45") (name "Net-(LED1-7)") (class "Default")
      (node (ref "LED1") (pin "3") (pinfunction "7_3") (pintype "passive"))
      (node (ref "R34") (pin "2") (pinfunction "2_2") (pintype "passive"))
    )
    (net (code "46") (name "Net-(LED1-8)") (class "Default")
      (node (ref "LED1") (pin "13") (pinfunction "8_13") (pintype "passive"))
      (node (ref "R33") (pin "2") (pinfunction "2_2") (pintype "passive"))
    )
    (net (code "47") (name "Net-(LED2-1)") (class "Default")
      (node (ref "LED2") (pin "16") (pinfunction "1_16") (pintype "passive"))
      (node (ref "R32") (pin "2") (pinfunction "2_2") (pintype "passive"))
    )
    (net (code "48") (name "Net-(LED2-2)") (class "Default")
      (node (ref "LED2") (pin "15") (pinfunction "2_15") (pintype "passive"))
      (node (ref "R31") (pin "2") (pinfunction "2_2") (pintype "passive"))
    )
    (net (code "49") (name "Net-(LED2-3)") (class "Default")
      (node (ref "LED2") (pin "11") (pinfunction "3_11") (pintype "passive"))
      (node (ref "R30") (pin "2") (pinfunction "2_2") (pintype "passive"))
    )
    (net (code "50") (name "Net-(LED2-4)") (class "Default")
      (node (ref "LED2") (pin "6") (pinfunction "4_6") (pintype "passive"))
      (node (ref "R29") (pin "2") (pinfunction "2_2") (pintype "passive"))
    )
    (net (code "51") (name "Net-(LED2-5)") (class "Default")
      (node (ref "LED2") (pin "10") (pinfunction "5_10") (pintype "passive"))
      (node (ref "R28") (pin "2") (pinfunction "2_2") (pintype "passive"))
    )
    (net (code "52") (name "Net-(LED2-6)") (class "Default")
      (node (ref "LED2") (pin "4") (pinfunction "6_4") (pintype "passive"))
      (node (ref "R27") (pin "2") (pinfunction "2_2") (pintype "passive"))
    )
    (net (code "53") (name "Net-(LED2-7)") (class "Default")
      (node (ref "LED2") (pin "3") (pinfunction "7_3") (pintype "passive"))
      (node (ref "R26") (pin "2") (pinfunction "2_2") (pintype "passive"))
    )
    (net (code "54") (name "Net-(LED2-8)") (class "Default")
      (node (ref "LED2") (pin "13") (pinfunction "8_13") (pintype "passive"))
      (node (ref "R25") (pin "2") (pinfunction "2_2") (pintype "passive"))
    )
    (net (code "55") (name "Net-(LED3-1)") (class "Default")
      (node (ref "LED3") (pin "16") (pinfunction "1_16") (pintype "passive"))
      (node (ref "R24") (pin "2") (pinfunction "2_2") (pintype "passive"))
    )
    (net (code "56") (name "Net-(LED3-2)") (class "Default")
      (node (ref "LED3") (pin "15") (pinfunction "2_15") (pintype "passive"))
      (node (ref "R23") (pin "2") (pinfunction "2_2") (pintype "passive"))
    )
    (net (code "57") (name "Net-(LED3-3)") (class "Default")
      (node (ref "LED3") (pin "11") (pinfunction "3_11") (pintype "passive"))
      (node (ref "R22") (pin "2") (pinfunction "2_2") (pintype "passive"))
    )
    (net (code "58") (name "Net-(LED3-4)") (class "Default")
      (node (ref "LED3") (pin "6") (pinfunction "4_6") (pintype "passive"))
      (node (ref "R21") (pin "2") (pinfunction "2_2") (pintype "passive"))
    )
    (net (code "59") (name "Net-(LED3-5)") (class "Default")
      (node (ref "LED3") (pin "10") (pinfunction "5_10") (pintype "passive"))
      (node (ref "R20") (pin "2") (pinfunction "2_2") (pintype "passive"))
    )
    (net (code "60") (name "Net-(LED3-6)") (class "Default")
      (node (ref "LED3") (pin "4") (pinfunction "6_4") (pintype "passive"))
      (node (ref "R19") (pin "2") (pinfunction "2_2") (pintype "passive"))
    )
    (net (code "61") (name "Net-(LED3-7)") (class "Default")
      (node (ref "LED3") (pin "3") (pinfunction "7_3") (pintype "passive"))
      (node (ref "R18") (pin "2") (pinfunction "2_2") (pintype "passive"))
    )
    (net (code "62") (name "Net-(LED3-8)") (class "Default")
      (node (ref "LED3") (pin "13") (pinfunction "8_13") (pintype "passive"))
      (node (ref "R17") (pin "2") (pinfunction "2_2") (pintype "passive"))
    )
    (net (code "63") (name "Net-(LED4-1)") (class "Default")
      (node (ref "LED4") (pin "16") (pinfunction "1_16") (pintype "passive"))
      (node (ref "R16") (pin "2") (pinfunction "2_2") (pintype "passive"))
    )
    (net (code "64") (name "Net-(LED4-2)") (class "Default")
      (node (ref "LED4") (pin "15") (pinfunction "2_15") (pintype "passive"))
      (node (ref "R15") (pin "2") (pinfunction "2_2") (pintype "passive"))
    )
    (net (code "65") (name "Net-(LED4-3)") (class "Default")
      (node (ref "LED4") (pin "11") (pinfunction "3_11") (pintype "passive"))
      (node (ref "R14") (pin "2") (pinfunction "2_2") (pintype "passive"))
    )
    (net (code "66") (name "Net-(LED4-4)") (class "Default")
      (node (ref "LED4") (pin "6") (pinfunction "4_6") (pintype "passive"))
      (node (ref "R13") (pin "2") (pinfunction "2_2") (pintype "passive"))
    )
    (net (code "67") (name "Net-(LED4-5)") (class "Default")
      (node (ref "LED4") (pin "10") (pinfunction "5_10") (pintype "passive"))
      (node (ref "R12") (pin "2") (pinfunction "2_2") (pintype "passive"))
    )
    (net (code "68") (name "Net-(LED4-6)") (class "Default")
      (node (ref "LED4") (pin "4") (pinfunction "6_4") (pintype "passive"))
      (node (ref "R11") (pin "2") (pinfunction "2_2") (pintype "passive"))
    )
    (net (code "69") (name "Net-(LED4-7)") (class "Default")
      (node (ref "LED4") (pin "3") (pinfunction "7_3") (pintype "passive"))
      (node (ref "R10") (pin "2") (pinfunction "2_2") (pintype "passive"))
    )
    (net (code "70") (name "Net-(LED4-8)") (class "Default")
      (node (ref "LED4") (pin "13") (pinfunction "8_13") (pintype "passive"))
      (node (ref "R9") (pin "2") (pinfunction "2_2") (pintype "passive"))
    )
    (net (code "71") (name "Net-(U1-AREF)") (class "Default")
      (node (ref "C2") (pin "2") (pinfunction "2_2") (pintype "passive"))
      (node (ref "U1") (pin "20") (pinfunction "AREF_20") (pintype "passive"))
    )
    (net (code "72") (name "Net-(U1-PB6)") (class "Default")
      (node (ref "C3") (pin "2") (pinfunction "2_2") (pintype "passive"))
      (node (ref "R2") (pin "2") (pinfunction "2_2") (pintype "passive"))
      (node (ref "U1") (pin "7") (pinfunction "PB6_7") (pintype "passive"))
      (node (ref "X1") (pin "1") (pinfunction "1_1") (pintype "passive"))
    )
    (net (code "73") (name "Net-(U1-PB7)") (class "Default")
      (node (ref "C4") (pin "2") (pinfunction "2_2") (pintype "passive"))
      (node (ref "R2") (pin "1") (pinfunction "1_1") (pintype "passive"))
      (node (ref "U1") (pin "8") (pinfunction "PB7_8") (pintype "passive"))
      (node (ref "X1") (pin "2") (pinfunction "2_2") (pintype "passive"))
    )
    (net (code "74") (name "Net-(U2-X1)") (class "Default")
      (node (ref "U2") (pin "1") (pinfunction "X1_1") (pintype "passive"))
      (node (ref "X2") (pin "1") (pinfunction "OSC1_1") (pintype "passive"))
    )
    (net (code "75") (name "Net-(U2-X2)") (class "Default")
      (node (ref "U2") (pin "2") (pinfunction "X2_2") (pintype "passive"))
      (node (ref "X2") (pin "4") (pinfunction "OSC2_4") (pintype "passive"))
    )
    (net (code "76") (name "Net-(U3-V3)") (class "Default")
      (node (ref "C9") (pin "2") (pinfunction "2_2") (pintype "passive"))
      (node (ref "U3") (pin "4") (pinfunction "V3_4") (pintype "passive"))
    )
    (net (code "77") (name "Net-(U5-QA)") (class "Default")
      (node (ref "R16") (pin "1") (pinfunction "1_1") (pintype "passive"))
      (node (ref "U5") (pin "15") (pinfunction "QA_15") (pintype "passive"))
    )
    (net (code "78") (name "Net-(U5-QB)") (class "Default")
      (node (ref "R15") (pin "1") (pinfunction "1_1") (pintype "passive"))
      (node (ref "U5") (pin "1") (pinfunction "QB_1") (pintype "passive"))
    )
    (net (code "79") (name "Net-(U5-QC)") (class "Default")
      (node (ref "R14") (pin "1") (pinfunction "1_1") (pintype "passive"))
      (node (ref "U5") (pin "2") (pinfunction "QC_2") (pintype "passive"))
    )
    (net (code "80") (name "Net-(U5-QD)") (class "Default")
      (node (ref "R13") (pin "1") (pinfunction "1_1") (pintype "passive"))
      (node (ref "U5") (pin "3") (pinfunction "QD_3") (pintype "passive"))
    )
    (net (code "81") (name "Net-(U5-QE)") (class "Default")
      (node (ref "R12") (pin "1") (pinfunction "1_1") (pintype "passive"))
      (node (ref "U5") (pin "4") (pinfunction "QE_4") (pintype "passive"))
    )
    (net (code "82") (name "Net-(U5-QF)") (class "Default")
      (node (ref "R11") (pin "1") (pinfunction "1_1") (pintype "passive"))
      (node (ref "U5") (pin "5") (pinfunction "QF_5") (pintype "passive"))
    )
    (net (code "83") (name "Net-(U5-QG)") (class "Default")
      (node (ref "R10") (pin "1") (pinfunction "1_1") (pintype "passive"))
      (node (ref "U5") (pin "6") (pinfunction "QG_6") (pintype "passive"))
    )
    (net (code "84") (name "Net-(U5-QH)") (class "Default")
      (node (ref "R9") (pin "1") (pinfunction "1_1") (pintype "passive"))
      (node (ref "U5") (pin "7") (pinfunction "QH_7") (pintype "passive"))
    )
    (net (code "85") (name "Net-(U5-SI)") (class "Default")
      (node (ref "U5") (pin "14") (pinfunction "SI_14") (pintype "passive"))
      (node (ref "U6") (pin "9") (pinfunction "SQH_9") (pintype "passive"))
    )
    (net (code "86") (name "Net-(U6-QA)") (class "Default")
      (node (ref "R24") (pin "1") (pinfunction "1_1") (pintype "passive"))
      (node (ref "U6") (pin "15") (pinfunction "QA_15") (pintype "passive"))
    )
    (net (code "87") (name "Net-(U6-QB)") (class "Default")
      (node (ref "R23") (pin "1") (pinfunction "1_1") (pintype "passive"))
      (node (ref "U6") (pin "1") (pinfunction "QB_1") (pintype "passive"))
    )
    (net (code "88") (name "Net-(U6-QC)") (class "Default")
      (node (ref "R22") (pin "1") (pinfunction "1_1") (pintype "passive"))
      (node (ref "U6") (pin "2") (pinfunction "QC_2") (pintype "passive"))
    )
    (net (code "89") (name "Net-(U6-QD)") (class "Default")
      (node (ref "R21") (pin "1") (pinfunction "1_1") (pintype "passive"))
      (node (ref "U6") (pin "3") (pinfunction "QD_3") (pintype "passive"))
    )
    (net (code "90") (name "Net-(U6-QE)") (class "Default")
      (node (ref "R20") (pin "1") (pinfunction "1_1") (pintype "passive"))
      (node (ref "U6") (pin "4") (pinfunction "QE_4") (pintype "passive"))
    )
    (net (code "91") (name "Net-(U6-QF)") (class "Default")
      (node (ref "R19") (pin "1") (pinfunction "1_1") (pintype "passive"))
      (node (ref "U6") (pin "5") (pinfunction "QF_5") (pintype "passive"))
    )
    (net (code "92") (name "Net-(U6-QG)") (class "Default")
      (node (ref "R18") (pin "1") (pinfunction "1_1") (pintype "passive"))
      (node (ref "U6") (pin "6") (pinfunction "QG_6") (pintype "passive"))
    )
    (net (code "93") (name "Net-(U6-QH)") (class "Default")
      (node (ref "R17") (pin "1") (pinfunction "1_1") (pintype "passive"))
      (node (ref "U6") (pin "7") (pinfunction "QH_7") (pintype "passive"))
    )
    (net (code "94") (name "Net-(U6-SI)") (class "Default")
      (node (ref "U6") (pin "14") (pinfunction "SI_14") (pintype "passive"))
      (node (ref "U7") (pin "9") (pinfunction "SQH_9") (pintype "passive"))
    )
    (net (code "95") (name "Net-(U7-QA)") (class "Default")
      (node (ref "R32") (pin "1") (pinfunction "1_1") (pintype "passive"))
      (node (ref "U7") (pin "15") (pinfunction "QA_15") (pintype "passive"))
    )
    (net (code "96") (name "Net-(U7-QB)") (class "Default")
      (node (ref "R31") (pin "1") (pinfunction "1_1") (pintype "passive"))
      (node (ref "U7") (pin "1") (pinfunction "QB_1") (pintype "passive"))
    )
    (net (code "97") (name "Net-(U7-QC)") (class "Default")
      (node (ref "R30") (pin "1") (pinfunction "1_1") (pintype "passive"))
      (node (ref "U7") (pin "2") (pinfunction "QC_2") (pintype "passive"))
    )
    (net (code "98") (name "Net-(U7-QD)") (class "Default")
      (node (ref "R29") (pin "1") (pinfunction "1_1") (pintype "passive"))
      (node (ref "U7") (pin "3") (pinfunction "QD_3") (pintype "passive"))
    )
    (net (code "99") (name "Net-(U7-QE)") (class "Default")
      (node (ref "R28") (pin "1") (pinfunction "1_1") (pintype "passive"))
      (node (ref "U7") (pin "4") (pinfunction "QE_4") (pintype "passive"))
    )
    (net (code "100") (name "Net-(U7-QF)") (class "Default")
      (node (ref "R27") (pin "1") (pinfunction "1_1") (pintype "passive"))
      (node (ref "U7") (pin "5") (pinfunction "QF_5") (pintype "passive"))
    )
    (net (code "101") (name "Net-(U7-QG)") (class "Default")
      (node (ref "R26") (pin "1") (pinfunction "1_1") (pintype "passive"))
      (node (ref "U7") (pin "6") (pinfunction "QG_6") (pintype "passive"))
    )
    (net (code "102") (name "Net-(U7-QH)") (class "Default")
      (node (ref "R25") (pin "1") (pinfunction "1_1") (pintype "passive"))
      (node (ref "U7") (pin "7") (pinfunction "QH_7") (pintype "passive"))
    )
    (net (code "103") (name "Net-(U7-SI)") (class "Default")
      (node (ref "U7") (pin "14") (pinfunction "SI_14") (pintype "passive"))
      (node (ref "U8") (pin "9") (pinfunction "SQH_9") (pintype "passive"))
    )
    (net (code "104") (name "Net-(U8-QA)") (class "Default")
      (node (ref "R40") (pin "1") (pinfunction "1_1") (pintype "passive"))
      (node (ref "U8") (pin "15") (pinfunction "QA_15") (pintype "passive"))
    )
    (net (code "105") (name "Net-(U8-QB)") (class "Default")
      (node (ref "R39") (pin "1") (pinfunction "1_1") (pintype "passive"))
      (node (ref "U8") (pin "1") (pinfunction "QB_1") (pintype "passive"))
    )
    (net (code "106") (name "Net-(U8-QC)") (class "Default")
      (node (ref "R38") (pin "1") (pinfunction "1_1") (pintype "passive"))
      (node (ref "U8") (pin "2") (pinfunction "QC_2") (pintype "passive"))
    )
    (net (code "107") (name "Net-(U8-QD)") (class "Default")
      (node (ref "R37") (pin "1") (pinfunction "1_1") (pintype "passive"))
      (node (ref "U8") (pin "3") (pinfunction "QD_3") (pintype "passive"))
    )
    (net (code "108") (name "Net-(U8-QE)") (class "Default")
      (node (ref "R36") (pin "1") (pinfunction "1_1") (pintype "passive"))
      (node (ref "U8") (pin "4") (pinfunction "QE_4") (pintype "passive"))
    )
    (net (code "109") (name "Net-(U8-QF)") (class "Default")
      (node (ref "R35") (pin "1") (pinfunction "1_1") (pintype "passive"))
      (node (ref "U8") (pin "5") (pinfunction "QF_5") (pintype "passive"))
    )
    (net (code "110") (name "Net-(U8-QG)") (class "Default")
      (node (ref "R34") (pin "1") (pinfunction "1_1") (pintype "passive"))
      (node (ref "U8") (pin "6") (pinfunction "QG_6") (pintype "passive"))
    )
    (net (code "111") (name "Net-(U8-QH)") (class "Default")
      (node (ref "R33") (pin "1") (pinfunction "1_1") (pintype "passive"))
      (node (ref "U8") (pin "7") (pinfunction "QH_7") (pintype "passive"))
    )
    (net (code "112") (name "unconnected-(KEY1-Pad3)") (class "Default")
      (node (ref "KEY1") (pin "3") (pinfunction "3_3") (pintype "passive"))
    )
    (net (code "113") (name "unconnected-(KEY1-Pad4)") (class "Default")
      (node (ref "KEY1") (pin "4") (pinfunction "4_4") (pintype "passive"))
    )
    (net (code "114") (name "unconnected-(KEY2-Pad3)") (class "Default")
      (node (ref "KEY2") (pin "3") (pinfunction "3_3") (pintype "passive"))
    )
    (net (code "115") (name "unconnected-(KEY2-Pad4)") (class "Default")
      (node (ref "KEY2") (pin "4") (pinfunction "4_4") (pintype "passive"))
    )
    (net (code "116") (name "unconnected-(KEY3-Pad3)") (class "Default")
      (node (ref "KEY3") (pin "3") (pinfunction "3_3") (pintype "passive"))
    )
    (net (code "117") (name "unconnected-(KEY3-Pad4)") (class "Default")
      (node (ref "KEY3") (pin "4") (pinfunction "4_4") (pintype "passive"))
    )
    (net (code "118") (name "unconnected-(KEY4-Pad3)") (class "Default")
      (node (ref "KEY4") (pin "3") (pinfunction "3_3") (pintype "passive"))
    )
    (net (code "119") (name "unconnected-(KEY4-Pad4)") (class "Default")
      (node (ref "KEY4") (pin "4") (pinfunction "4_4") (pintype "passive"))
    )
    (net (code "120") (name "unconnected-(U1-ADC6-Pad19)") (class "Default")
      (node (ref "U1") (pin "19") (pinfunction "ADC6_19") (pintype "passive+no_connect"))
    )
    (net (code "121") (name "unconnected-(U1-ADC7-Pad22)") (class "Default")
      (node (ref "U1") (pin "22") (pinfunction "ADC7_22") (pintype "passive+no_connect"))
    )
    (net (code "122") (name "unconnected-(U3-CTS#-Pad9)") (class "Default")
      (node (ref "U3") (pin "9") (pinfunction "CTS#_9") (pintype "passive"))
    )
    (net (code "123") (name "unconnected-(U3-DCD#-Pad12)") (class "Default")
      (node (ref "U3") (pin "12") (pinfunction "DCD#_12") (pintype "passive"))
    )
    (net (code "124") (name "unconnected-(U3-DSR#-Pad10)") (class "Default")
      (node (ref "U3") (pin "10") (pinfunction "DSR#_10") (pintype "passive"))
    )
    (net (code "125") (name "unconnected-(U3-NC-Pad7)") (class "Default")
      (node (ref "U3") (pin "7") (pinfunction "NC_7") (pintype "passive"))
    )
    (net (code "126") (name "unconnected-(U3-NC-Pad8)") (class "Default")
      (node (ref "U3") (pin "8") (pinfunction "NC_8") (pintype "passive"))
    )
    (net (code "127") (name "unconnected-(U3-R232-Pad15)") (class "Default")
      (node (ref "U3") (pin "15") (pinfunction "R232_15") (pintype "passive"))
    )
    (net (code "128") (name "unconnected-(U3-RI#-Pad11)") (class "Default")
      (node (ref "U3") (pin "11") (pinfunction "RI#_11") (pintype "passive"))
    )
    (net (code "129") (name "unconnected-(U3-RTS#-Pad14)") (class "Default")
      (node (ref "U3") (pin "14") (pinfunction "RTS#_14") (pintype "passive"))
    )
    (net (code "130") (name "unconnected-(U4-NC-Pad3)") (class "Default")
      (node (ref "U4") (pin "3") (pinfunction "NC_3") (pintype "passive"))
    )
    (net (code "131") (name "unconnected-(U5-SQH-Pad9)") (class "Default")
      (node (ref "U5") (pin "9") (pinfunction "SQH_9") (pintype "passive"))
    )
    (net (code "132") (name "unconnected-(USB1-ID-Pad4)") (class "Default")
      (node (ref "USB1") (pin "4") (pinfunction "ID_4") (pintype "passive"))
    )
  )
)
